# LED.net
KiCad netlist of a schematic drawn in Altium Designer
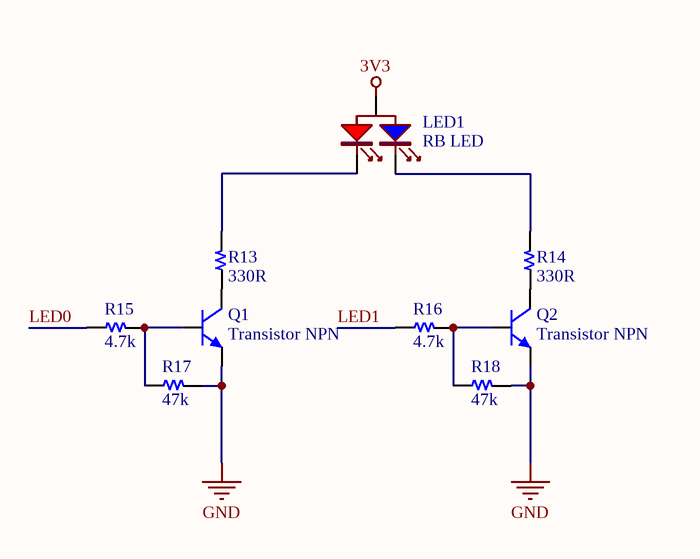
[diagram p0: LED.SchDoc]

(export (version "E")
  (design (tool "Eeschema 10.0.6"))
  (components
    (comp (ref "LED1")
      (value "RB LED")
      (footprint "LED-BICOLOR-3MM")
      (description "Bicolor RB 3mm LED")
      (libsource (lib "led") (part "LED 2-color-A"))
    )
    (comp (ref "Q1")
      (value "Transistor NPN")
      (footprint "SOT-23")
      (description "NPN Bipolar Transistor")
      (libsource (lib "chipfc_libs") (part "Transistor NPN"))
    )
    (comp (ref "Q2")
      (value "Transistor NPN")
      (footprint "SOT-23")
      (description "NPN Bipolar Transistor")
      (libsource (lib "chipfc_libs") (part "Transistor NPN"))
    )
    (comp (ref "R13")
      (value "330R")
      (footprint "R 0603")
      (description "Resistor")
      (libsource (lib "chipfc_libs") (part "Resistor"))
    )
    (comp (ref "R14")
      (value "330R")
      (footprint "R 0603")
      (description "Resistor")
      (libsource (lib "chipfc_libs") (part "Resistor"))
    )
    (comp (ref "R15")
      (value "4.7k")
      (footprint "R 0603")
      (description "Resistor")
      (libsource (lib "chipfc_libs") (part "Resistor"))
    )
    (comp (ref "R16")
      (value "4.7k")
      (footprint "R 0603")
      (description "Resistor")
      (libsource (lib "chipfc_libs") (part "Resistor"))
    )
    (comp (ref "R17")
      (value "47k")
      (footprint "R 0603")
      (description "Resistor")
      (libsource (lib "chipfc_libs") (part "Resistor"))
    )
    (comp (ref "R18")
      (value "47k")
      (footprint "R 0603")
      (description "Resistor")
      (libsource (lib "chipfc_libs") (part "Resistor"))
    )
  )
  (nets
    (net (code "1") (name "/LED0") (class "Default")
      (node (ref "R15") (pin "1") (pinfunction "1_1") (pintype "passive"))
    )
    (net (code "2") (name "/LED1") (class "Default")
      (node (ref "R16") (pin "1") (pinfunction "1_1") (pintype "passive"))
    )
    (net (code "3") (name "3V3") (class "Default")
      (node (ref "LED1") (pin "2") (pinfunction "A_2") (pintype "passive"))
    )
    (net (code "4") (name "GND") (class "Default")
      (node (ref "Q1") (pin "2") (pinfunction "E_2") (pintype "passive"))
      (node (ref "Q2") (pin "2") (pinfunction "E_2") (pintype "passive"))
      (node (ref "R17") (pin "2") (pinfunction "2_2") (pintype "passive"))
      (node (ref "R18") (pin "2") (pinfunction "2_2") (pintype "passive"))
    )
    (net (code "5") (name "Net-(LED1-K1)") (class "Default")
      (node (ref "LED1") (pin "1") (pinfunction "K1_1") (pintype "passive"))
      (node (ref "R13") (pin "2") (pinfunction "2_2") (pintype "passive"))
    )
    (net (code "6") (name "Net-(LED1-K2)") (class "Default")
      (node (ref "LED1") (pin "3") (pinfunction "K2_3") (pintype "passive"))
      (node (ref "R14") (pin "2") (pinfunction "2_2") (pintype "passive"))
    )
    (net (code "7") (name "Net-(Q1-B)") (class "Default")
      (node (ref "Q1") (pin "1") (pinfunction "B_1") (pintype "passive"))
      (node (ref "R15") (pin "2") (pinfunction "2_2") (pintype "passive"))
      (node (ref "R17") (pin "1") (pinfunction "1_1") (pintype "passive"))
    )
    (net (code "8") (name "Net-(Q1-C)") (class "Default")
      (node (ref "Q1") (pin "3") (pinfunction "C_3") (pintype "passive"))
      (node (ref "R13") (pin "1") (pinfunction "1_1") (pintype "passive"))
    )
    (net (code "9") (name "Net-(Q2-B)") (class "Default")
      (node (ref "Q2") (pin "1") (pinfunction "B_1") (pintype "passive"))
      (node (ref "R16") (pin "2") (pinfunction "2_2") (pintype "passive"))
      (node (ref "R18") (pin "1") (pinfunction "1_1") (pintype "passive"))
    )
    (net (code "10") (name "Net-(Q2-C)") (class "Default")
      (node (ref "Q2") (pin "3") (pinfunction "C_3") (pintype "passive"))
      (node (ref "R14") (pin "1") (pinfunction "1_1") (pintype "passive"))
    )
  )
)
